# BB_BME680.net
KiCad netlist of a schematic drawn in Altium Designer
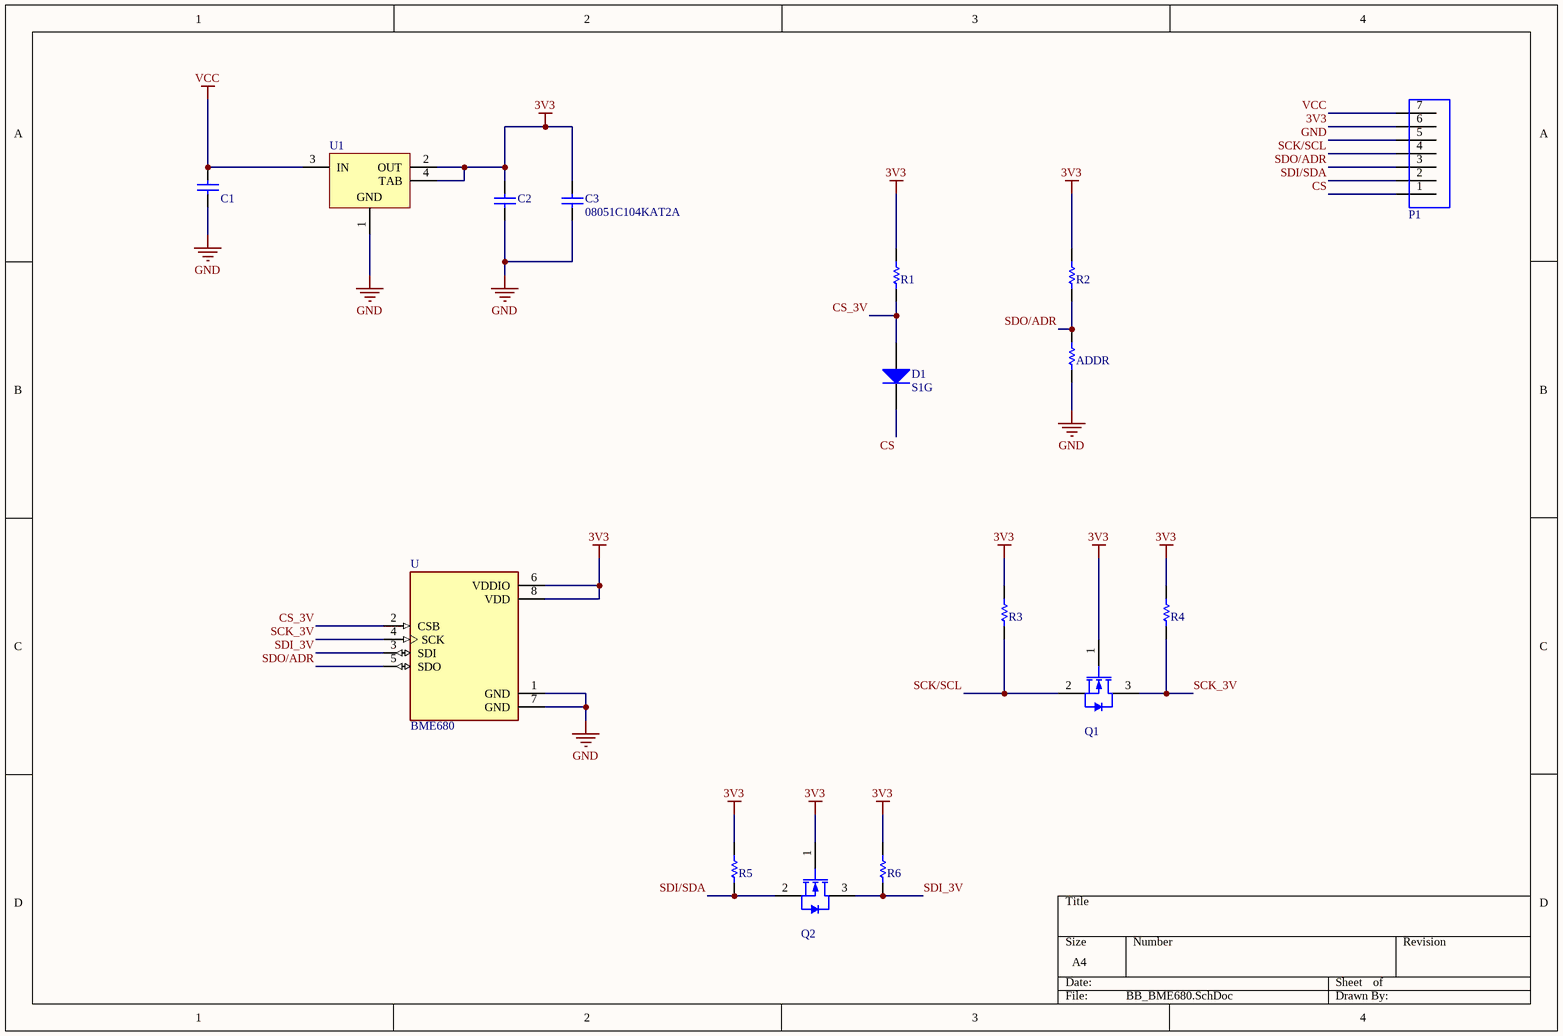
[diagram p0: BB_BME680.SchDoc]

(export (version "E")
  (design (tool "Eeschema 10.0.6"))
  (components
    (comp (ref "ADDR")
      (value "JUMPER")
      (footprint "RESC2013X60X30ML20T20")
      (fields (field (name "PART NUMBER") "RK73B2ATTD103J") (field (name "MANUFACTURER") "KOA Speer"))
      (libsource (lib "Altium Content Vault") (part "RES"))
    )
    (comp (ref "C1")
      (value "C0805C106K4PACTU")
      (footprint "CAPC2013X140X50ML20T25")
      (description "10µF ±10% 16V Ceramic Capacitor X5R 0805 (2012 Metric)")
      (fields (field (name "PART NUMBER") "CL21A106KOQNNNG"))
      (libsource (lib "Altium Content Vault") (part "CAP"))
    )
    (comp (ref "C2")
      (value "C0805C106K4PACTU")
      (footprint "CAPC2013X140X50ML20T25")
      (description "10µF ±10% 16V Ceramic Capacitor X5R 0805 (2012 Metric)")
      (fields (field (name "PART NUMBER") "CL21A106KOQNNNG"))
      (libsource (lib "Altium Content Vault") (part "CAP"))
    )
    (comp (ref "C3")
      (value "08051C104KAT2A")
      (footprint "CAPC2013X94X50ML20T25")
      (fields (field (name "MANUFACTURER") "AVX Interconnect / Elco"))
      (libsource (lib "Altium Content Vault") (part "CAP"))
    )
    (comp (ref "D1")
      (value "S1G")
      (footprint "FAIR-DO-214AC-2_V")
      (description "General Purpose Rectifier, 1.4 W, -55 to 150 degC, 2-Pin DO-214AC, RoHS, Tape and Reel")
      (fields (field (name "MANUFACTURER") "Fairchild Semiconductor"))
      (libsource (lib "Altium Content Vault") (part "FAIR-S1G-2"))
    )
    (comp (ref "P1")
      (value "PIN_HEADER_7")
      (footprint "PIN_HEADER_7")
      (libsource (lib "BB_LIBRERIA") (part "PIN_HEADER_7"))
    )
    (comp (ref "Q1")
      (value "BSS138-7-F")
      (footprint "DIOD-SOT23-3_V")
      (description "N-Channel Enhancement Mode Mosfet, 50 V, 0.2 A, -55 to 150 degC, 3-Pin SOT23, RoHS, Tape and Reel")
      (fields (field (name "MANUFACTURER") "Diodes Inc"))
      (libsource (lib "Altium Content Vault") (part "NEMOS-GSD-3"))
    )
    (comp (ref "Q2")
      (value "BSS138-7-F")
      (footprint "DIOD-SOT23-3_V")
      (description "N-Channel Enhancement Mode Mosfet, 50 V, 0.2 A, -55 to 150 degC, 3-Pin SOT23, RoHS, Tape and Reel")
      (fields (field (name "MANUFACTURER") "Diodes Inc"))
      (libsource (lib "Altium Content Vault") (part "NEMOS-GSD-3"))
    )
    (comp (ref "R1")
      (value "RK73B2ATTD103J")
      (footprint "RESC2013X60X30ML20T20")
      (fields (field (name "MANUFACTURER") "KOA Speer"))
      (libsource (lib "Altium Content Vault") (part "RES"))
    )
    (comp (ref "R2")
      (value "RK73B2ATTD103J")
      (footprint "RESC2013X60X30ML20T20")
      (fields (field (name "MANUFACTURER") "KOA Speer"))
      (libsource (lib "Altium Content Vault") (part "RES"))
    )
    (comp (ref "R3")
      (value "RK73B2ATTD103J")
      (footprint "RESC2013X60X30ML20T20")
      (fields (field (name "MANUFACTURER") "KOA Speer"))
      (libsource (lib "Altium Content Vault") (part "RES"))
    )
    (comp (ref "R4")
      (value "RK73B2ATTD103J")
      (footprint "RESC2013X60X30ML20T20")
      (fields (field (name "MANUFACTURER") "KOA Speer"))
      (libsource (lib "Altium Content Vault") (part "RES"))
    )
    (comp (ref "R5")
      (value "RK73B2ATTD103J")
      (footprint "RESC2013X60X30ML20T20")
      (fields (field (name "MANUFACTURER") "KOA Speer"))
      (libsource (lib "Altium Content Vault") (part "RES"))
    )
    (comp (ref "R6")
      (value "RK73B2ATTD103J")
      (footprint "RESC2013X60X30ML20T20")
      (fields (field (name "MANUFACTURER") "KOA Speer"))
      (libsource (lib "Altium Content Vault") (part "RES"))
    )
    (comp (ref "U")
      (value "BME680")
      (footprint "SnapEDApcb:BME680")
      (description "Gas, Humidity, Pressure, Temperature Sensor IÂ²C, SPI Output")
      (fields (field (name "MF") "Bosch Sensortec"))
      (libsource (lib "SnapEDAsch") (part "BME680"))
    )
    (comp (ref "U1")
      (value "LM1117MPX-3.3/NOPB")
      (footprint "DCY0004A_L")
      (description "800mA Low-Dropout Linear Regulator, 4-pin SOT-223, Pb-Free")
      (fields (field (name "MANUFACTURER") "Texas Instruments"))
      (libsource (lib "Altium Content Vault") (part "PM-REG-LM1086-SOT4"))
    )
  )
  (nets
    (net (code "1") (name "/CS") (class "Default")
      (node (ref "D1") (pin "2") (pinfunction "K_2") (pintype "passive"))
      (node (ref "P1") (pin "1") (pinfunction "1_1") (pintype "passive"))
    )
    (net (code "2") (name "/CS_3V") (class "Default")
      (node (ref "D1") (pin "1") (pinfunction "A_1") (pintype "passive"))
      (node (ref "R1") (pin "2") (pinfunction "2_2") (pintype "passive"))
      (node (ref "U") (pin "2") (pinfunction "CSB_2") (pintype "input"))
    )
    (net (code "3") (name "/SCK_3V") (class "Default")
      (node (ref "Q1") (pin "3") (pinfunction "D_3") (pintype "passive"))
      (node (ref "R4") (pin "2") (pinfunction "2_2") (pintype "passive"))
      (node (ref "U") (pin "4") (pinfunction "SCK_4") (pintype "input"))
    )
    (net (code "4") (name "/SCK{slash}SCL") (class "Default")
      (node (ref "P1") (pin "4") (pinfunction "4_4") (pintype "passive"))
      (node (ref "Q1") (pin "2") (pinfunction "S_2") (pintype "passive"))
      (node (ref "R3") (pin "2") (pinfunction "2_2") (pintype "passive"))
    )
    (net (code "5") (name "/SDI_3V") (class "Default")
      (node (ref "Q2") (pin "3") (pinfunction "D_3") (pintype "passive"))
      (node (ref "R6") (pin "2") (pinfunction "2_2") (pintype "passive"))
      (node (ref "U") (pin "3") (pinfunction "SDI_3") (pintype "bidirectional"))
    )
    (net (code "6") (name "/SDI{slash}SDA") (class "Default")
      (node (ref "P1") (pin "2") (pinfunction "2_2") (pintype "passive"))
      (node (ref "Q2") (pin "2") (pinfunction "S_2") (pintype "passive"))
      (node (ref "R5") (pin "2") (pinfunction "2_2") (pintype "passive"))
    )
    (net (code "7") (name "/SDO{slash}ADR") (class "Default")
      (node (ref "ADDR") (pin "1") (pinfunction "1_1") (pintype "passive"))
      (node (ref "P1") (pin "3") (pinfunction "3_3") (pintype "passive"))
      (node (ref "R2") (pin "2") (pinfunction "2_2") (pintype "passive"))
      (node (ref "U") (pin "5") (pinfunction "SDO_5") (pintype "bidirectional"))
    )
    (net (code "8") (name "3V3") (class "Default")
      (node (ref "C2") (pin "2") (pinfunction "2_2") (pintype "passive"))
      (node (ref "C3") (pin "2") (pinfunction "2_2") (pintype "passive"))
      (node (ref "P1") (pin "6") (pinfunction "6_6") (pintype "passive"))
      (node (ref "Q1") (pin "1") (pinfunction "G_1") (pintype "passive"))
      (node (ref "Q2") (pin "1") (pinfunction "G_1") (pintype "passive"))
      (node (ref "R1") (pin "1") (pinfunction "1_1") (pintype "passive"))
      (node (ref "R2") (pin "1") (pinfunction "1_1") (pintype "passive"))
      (node (ref "R3") (pin "1") (pinfunction "1_1") (pintype "passive"))
      (node (ref "R4") (pin "1") (pinfunction "1_1") (pintype "passive"))
      (node (ref "R5") (pin "1") (pinfunction "1_1") (pintype "passive"))
      (node (ref "R6") (pin "1") (pinfunction "1_1") (pintype "passive"))
      (node (ref "U") (pin "6") (pinfunction "VDDIO_6") (pintype "power_in"))
      (node (ref "U") (pin "8") (pinfunction "VDD_8") (pintype "power_in"))
      (node (ref "U1") (pin "2") (pinfunction "OUT_2") (pintype "power_in"))
      (node (ref "U1") (pin "4") (pinfunction "TAB_4") (pintype "power_in"))
    )
    (net (code "9") (name "GND") (class "Default")
      (node (ref "ADDR") (pin "2") (pinfunction "2_2") (pintype "passive"))
      (node (ref "C1") (pin "2") (pinfunction "2_2") (pintype "passive"))
      (node (ref "C2") (pin "1") (pinfunction "1_1") (pintype "passive"))
      (node (ref "C3") (pin "1") (pinfunction "1_1") (pintype "passive"))
      (node (ref "P1") (pin "5") (pinfunction "5_5") (pintype "passive"))
      (node (ref "U") (pin "1") (pinfunction "GND_1") (pintype "power_in"))
      (node (ref "U") (pin "7") (pinfunction "GND_7") (pintype "power_in"))
      (node (ref "U1") (pin "1") (pinfunction "GND_1") (pintype "power_in"))
    )
    (net (code "10") (name "VCC") (class "Default")
      (node (ref "C1") (pin "1") (pinfunction "1_1") (pintype "passive"))
      (node (ref "P1") (pin "7") (pinfunction "7_7") (pintype "passive"))
      (node (ref "U1") (pin "3") (pinfunction "IN_3") (pintype "power_in"))
    )
  )
)
